# NavMergeBoard.net
KiCad netlist of a schematic drawn in Altium Designer
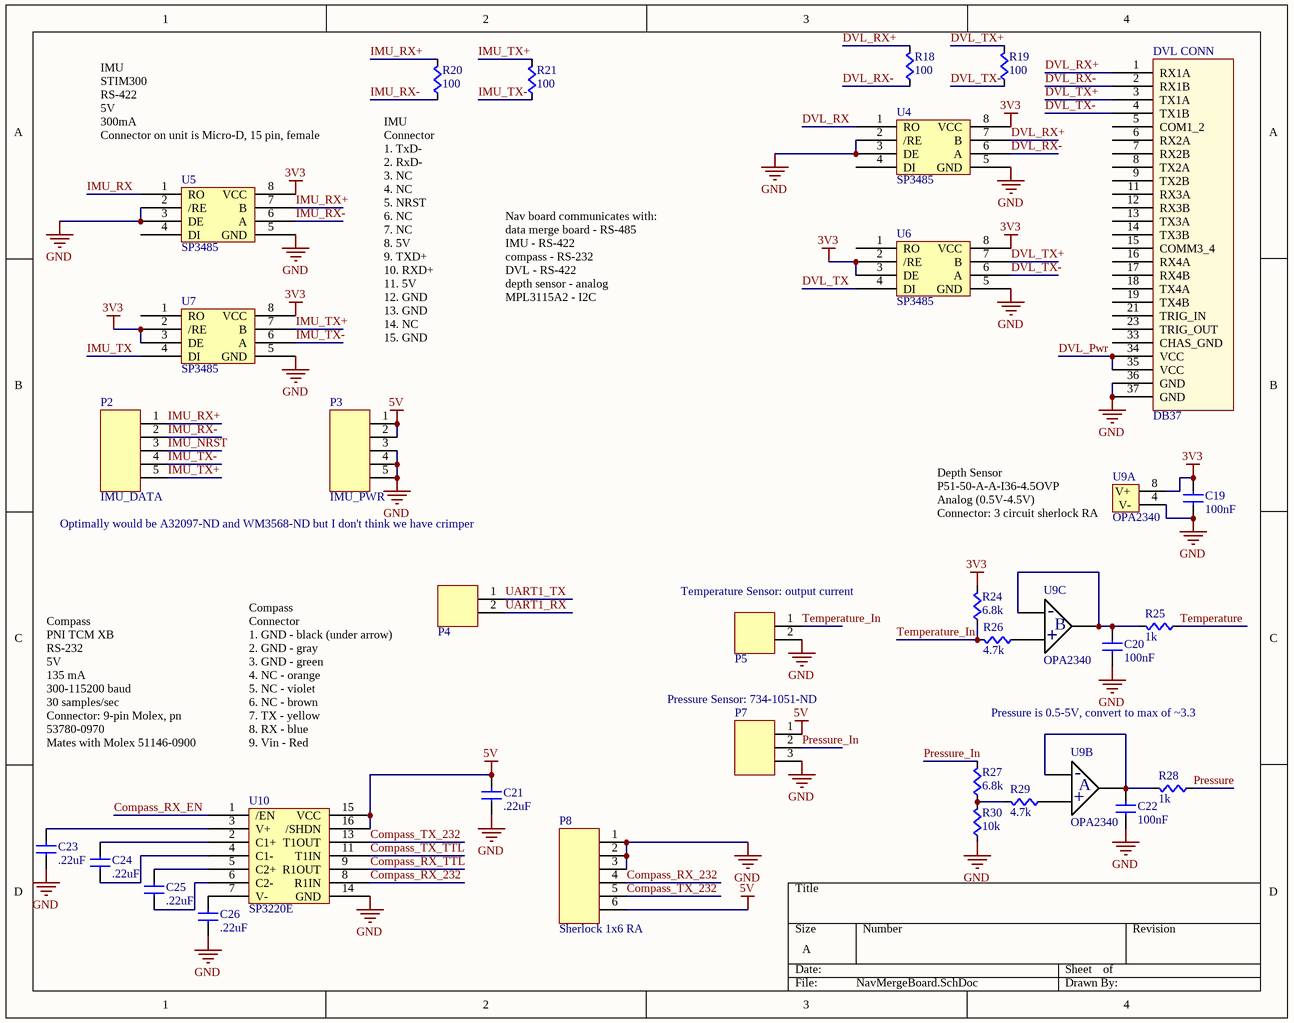
[diagram p0: NavMergeBoard.SchDoc]

(export (version "E")
  (design (tool "Eeschema 10.0.6"))
  (components
    (comp (ref "C19")
      (value "100nF")
      (footprint "CAPC0603")
      (fields (field (name "Comment") "Cap"))
      (libsource (lib "SubjuGator8") (part "Cap"))
    )
    (comp (ref "C20")
      (value "100nF")
      (footprint "CAPC0603")
      (fields (field (name "Comment") "Cap"))
      (libsource (lib "SubjuGator8") (part "Cap"))
    )
    (comp (ref "C21")
      (value ".22uF")
      (footprint "CAPC0603")
      (fields (field (name "Comment") "Cap"))
      (libsource (lib "SubjuGator8") (part "Cap"))
    )
    (comp (ref "C22")
      (value "100nF")
      (footprint "CAPC0603")
      (fields (field (name "Comment") "Cap"))
      (libsource (lib "SubjuGator8") (part "Cap"))
    )
    (comp (ref "C23")
      (value ".22uF")
      (footprint "CAPC0603")
      (fields (field (name "Comment") "Cap"))
      (libsource (lib "SubjuGator8") (part "Cap"))
    )
    (comp (ref "C24")
      (value ".22uF")
      (footprint "CAPC0603")
      (fields (field (name "Comment") "Cap"))
      (libsource (lib "SubjuGator8") (part "Cap"))
    )
    (comp (ref "C25")
      (value ".22uF")
      (footprint "CAPC0603")
      (fields (field (name "Comment") "Cap"))
      (libsource (lib "SubjuGator8") (part "Cap"))
    )
    (comp (ref "C26")
      (value ".22uF")
      (footprint "CAPC0603")
      (fields (field (name "Comment") "Cap"))
      (libsource (lib "SubjuGator8") (part "Cap"))
    )
    (comp (ref "DVL CONN")
      (value "DB37")
      (footprint "DSUB37_ FEMALE")
      (description "DVL Connector using DSUB37")
      (fields
        (field (name "MANUFACTURER") "FCI")
        (field (name "MANUFACTURER PART NUMBER") "10090098-S374VLF")
      )
      (libsource (lib "SubjuGator8") (part "DVLCONN"))
    )
    (comp (ref "P2")
      (value "MOLEX-HDR-1x5-SHERLOCK_RA")
      (footprint "MOLEX-HDR-1X5-SHERLOCK- RA")
      (fields (field (name "MANUFACTURER PART NUMBER") "0353630560") (field (name "MANUFACTURER") "Molex"))
      (libsource (lib "SubjuGator8") (part "MOLEX-HDR-1x5-SHERLOCK_RA"))
    )
    (comp (ref "P3")
      (value "MOLEX-HDR-1x5-SHERLOCK_RA")
      (footprint "MOLEX-HDR-1X5-SHERLOCK- RA")
      (fields (field (name "MANUFACTURER PART NUMBER") "0353630560") (field (name "MANUFACTURER") "Molex"))
      (libsource (lib "SubjuGator8") (part "MOLEX-HDR-1x5-SHERLOCK_RA"))
    )
    (comp (ref "P4")
      (value "2-pin Horz Sherlock")
      (footprint "MOLEX-HDR-1X2-SHERLOCK-HORZ")
      (fields
        (field (name "MANUFACTURER PART NUMBER") "0353630260")
        (field (name "MANUFACTURER") "Molex Inc")
      )
      (libsource (lib "SubjuGator8") (part "MOLEX-HDR-1x2-SHERLOCK_RA"))
    )
    (comp (ref "P5")
      (value "2-pin Horz Sherlock")
      (footprint "MOLEX-HDR-1X2-SHERLOCK-HORZ")
      (fields
        (field (name "MANUFACTURER PART NUMBER") "0353630260")
        (field (name "MANUFACTURER") "Molex Inc")
      )
      (libsource (lib "SubjuGator8") (part "MOLEX-HDR-1x2-SHERLOCK_RA"))
    )
    (comp (ref "P7")
      (value "3pos RA sherlock connector")
      (footprint "MOLEX-HDR-1X3-SHERLOCK-RA")
      (description "Header, Molex, 2mm Pitch Sherlock Header, Single Row, Right Angle 3 Circuits, Length 3.3mm")
      (fields
        (field (name "MANUFACTURER PART NUMBER") "35363-0360")
        (field (name "MANUFACTURER") "Molex Connector Corporation")
      )
      (libsource (lib "SubjuGator8") (part "MOLEX-HDR-1x3-SHERLOCK_RA"))
    )
    (comp (ref "P8")
      (value "Sherlock 1x6 RA")
      (footprint "MOLEX-HDR-1X6-SHERLOCK- RA")
      (description "CONN HEADER 6POS 2MM R/A TIN")
      (libsource (lib "SubjuGator8") (part "MOLEX-HDR-1x6-SHERLOCK_RA"))
    )
    (comp (ref "R18")
      (value "100")
      (footprint "RES0603")
      (fields (field (name "Comment") "Res"))
      (libsource (lib "SubjuGator8") (part "Res"))
    )
    (comp (ref "R19")
      (value "100")
      (footprint "RES0603")
      (fields (field (name "Comment") "Res"))
      (libsource (lib "SubjuGator8") (part "Res"))
    )
    (comp (ref "R20")
      (value "100")
      (footprint "RES0603")
      (fields (field (name "Comment") "Res"))
      (libsource (lib "SubjuGator8") (part "Res"))
    )
    (comp (ref "R21")
      (value "100")
      (footprint "RES0603")
      (fields (field (name "Comment") "Res"))
      (libsource (lib "SubjuGator8") (part "Res"))
    )
    (comp (ref "R24")
      (value "6.8k")
      (footprint "RES0603")
      (fields (field (name "Comment") "Res"))
      (libsource (lib "SubjuGator8") (part "Res"))
    )
    (comp (ref "R25")
      (value "1k")
      (footprint "RES0603")
      (fields (field (name "Comment") "Res"))
      (libsource (lib "SubjuGator8") (part "Res"))
    )
    (comp (ref "R26")
      (value "4.7k")
      (footprint "RES0603")
      (fields (field (name "Comment") "Res"))
      (libsource (lib "SubjuGator8") (part "Res"))
    )
    (comp (ref "R27")
      (value "6.8k")
      (footprint "RES0603")
      (fields (field (name "Comment") "Res"))
      (libsource (lib "SubjuGator8") (part "Res"))
    )
    (comp (ref "R28")
      (value "1k")
      (footprint "RES0603")
      (fields (field (name "Comment") "Res"))
      (libsource (lib "SubjuGator8") (part "Res"))
    )
    (comp (ref "R29")
      (value "4.7k")
      (footprint "RES0603")
      (fields (field (name "Comment") "Res"))
      (libsource (lib "SubjuGator8") (part "Res"))
    )
    (comp (ref "R30")
      (value "10k")
      (footprint "RES0603")
      (fields (field (name "Comment") "Res"))
      (libsource (lib "SubjuGator8") (part "Res"))
    )
    (comp (ref "U4")
      (value "SP3485")
      (footprint "SP3485")
      (description "IC TXRX RS485 HALF DUPLEX 8NSOIC")
      (libsource (lib "SubjuGator8") (part "SP3485"))
    )
    (comp (ref "U5")
      (value "SP3485")
      (footprint "SP3485")
      (description "IC TXRX RS485 HALF DUPLEX 8NSOIC")
      (libsource (lib "SubjuGator8") (part "SP3485"))
    )
    (comp (ref "U6")
      (value "SP3485")
      (footprint "SP3485")
      (description "IC TXRX RS485 HALF DUPLEX 8NSOIC")
      (libsource (lib "SubjuGator8") (part "SP3485"))
    )
    (comp (ref "U7")
      (value "SP3485")
      (footprint "SP3485")
      (description "IC TXRX RS485 HALF DUPLEX 8NSOIC")
      (libsource (lib "SubjuGator8") (part "SP3485"))
    )
    (comp (ref "U9")
      (value "OPA2340")
      (footprint "OPA2340")
      (description "IC OPAMP GP 5.5MHZ RRO 8SOIC")
      (libsource (lib "SubjuGator8") (part "OPA2340"))
    )
    (comp (ref "U10")
      (value "SP3220E")
      (footprint "SP3220ECY-L/TR")
      (description "IC DVR/RCVR RS232 ESD 16TSSOP")
      (libsource (lib "ICs") (part "SP3220E"))
    )
  )
  (nets
    (net (code "1") (name "/Compass_RX_232") (class "Default")
      (node (ref "P8") (pin "4") (pinfunction "4_4") (pintype "passive"))
      (node (ref "U10") (pin "8") (pinfunction "R1IN_8") (pintype "passive"))
    )
    (net (code "2") (name "/Compass_RX_EN") (class "Default")
      (node (ref "U10") (pin "1") (pinfunction "/EN_1") (pintype "passive"))
    )
    (net (code "3") (name "/Compass_RX_TTL") (class "Default")
      (node (ref "U10") (pin "9") (pinfunction "R1OUT_9") (pintype "passive"))
    )
    (net (code "4") (name "/Compass_TX_232") (class "Default")
      (node (ref "P8") (pin "5") (pinfunction "5_5") (pintype "passive"))
      (node (ref "U10") (pin "13") (pinfunction "T1OUT_13") (pintype "passive"))
    )
    (net (code "5") (name "/Compass_TX_TTL") (class "Default")
      (node (ref "U10") (pin "11") (pinfunction "T1IN_11") (pintype "passive"))
    )
    (net (code "6") (name "/DVL_Pwr") (class "Default")
      (node (ref "DVL CONN") (pin "34") (pinfunction "VCC_34") (pintype "passive"))
      (node (ref "DVL CONN") (pin "35") (pinfunction "VCC_35") (pintype "passive"))
    )
    (net (code "7") (name "/DVL_RX") (class "Default")
      (node (ref "U4") (pin "1") (pinfunction "RO_1") (pintype "passive"))
    )
    (net (code "8") (name "/DVL_RX+") (class "Default")
      (node (ref "DVL CONN") (pin "1") (pinfunction "RX1A_1") (pintype "passive"))
      (node (ref "R18") (pin "1") (pinfunction "A_1") (pintype "passive"))
      (node (ref "U4") (pin "7") (pinfunction "B_7") (pintype "passive"))
    )
    (net (code "9") (name "/DVL_RX-") (class "Default")
      (node (ref "DVL CONN") (pin "2") (pinfunction "RX1B_2") (pintype "passive"))
      (node (ref "R18") (pin "2") (pinfunction "B_2") (pintype "passive"))
      (node (ref "U4") (pin "6") (pinfunction "A_6") (pintype "passive"))
    )
    (net (code "10") (name "/DVL_TX") (class "Default")
      (node (ref "U6") (pin "4") (pinfunction "DI_4") (pintype "passive"))
    )
    (net (code "11") (name "/DVL_TX+") (class "Default")
      (node (ref "DVL CONN") (pin "3") (pinfunction "TX1A_3") (pintype "passive"))
      (node (ref "R19") (pin "1") (pinfunction "A_1") (pintype "passive"))
      (node (ref "U6") (pin "7") (pinfunction "B_7") (pintype "passive"))
    )
    (net (code "12") (name "/DVL_TX-") (class "Default")
      (node (ref "DVL CONN") (pin "4") (pinfunction "TX1B_4") (pintype "passive"))
      (node (ref "R19") (pin "2") (pinfunction "B_2") (pintype "passive"))
      (node (ref "U6") (pin "6") (pinfunction "A_6") (pintype "passive"))
    )
    (net (code "13") (name "/IMU_NRST") (class "Default")
      (node (ref "P2") (pin "3") (pinfunction "3_3") (pintype "passive"))
    )
    (net (code "14") (name "/IMU_RX") (class "Default")
      (node (ref "U5") (pin "1") (pinfunction "RO_1") (pintype "passive"))
    )
    (net (code "15") (name "/IMU_RX+") (class "Default")
      (node (ref "P2") (pin "1") (pinfunction "1_1") (pintype "passive"))
      (node (ref "R20") (pin "1") (pinfunction "A_1") (pintype "passive"))
      (node (ref "U5") (pin "7") (pinfunction "B_7") (pintype "passive"))
    )
    (net (code "16") (name "/IMU_RX-") (class "Default")
      (node (ref "P2") (pin "2") (pinfunction "2_2") (pintype "passive"))
      (node (ref "R20") (pin "2") (pinfunction "B_2") (pintype "passive"))
      (node (ref "U5") (pin "6") (pinfunction "A_6") (pintype "passive"))
    )
    (net (code "17") (name "/IMU_TX") (class "Default")
      (node (ref "U7") (pin "4") (pinfunction "DI_4") (pintype "passive"))
    )
    (net (code "18") (name "/IMU_TX+") (class "Default")
      (node (ref "P2") (pin "5") (pinfunction "5_5") (pintype "passive"))
      (node (ref "R21") (pin "1") (pinfunction "A_1") (pintype "passive"))
      (node (ref "U7") (pin "7") (pinfunction "B_7") (pintype "passive"))
    )
    (net (code "19") (name "/IMU_TX-") (class "Default")
      (node (ref "P2") (pin "4") (pinfunction "4_4") (pintype "passive"))
      (node (ref "R21") (pin "2") (pinfunction "B_2") (pintype "passive"))
      (node (ref "U7") (pin "6") (pinfunction "A_6") (pintype "passive"))
    )
    (net (code "20") (name "/Pressure") (class "Default")
      (node (ref "R28") (pin "2") (pinfunction "B_2") (pintype "passive"))
    )
    (net (code "21") (name "/Pressure_In") (class "Default")
      (node (ref "P7") (pin "2") (pinfunction "2_2") (pintype "passive"))
      (node (ref "R27") (pin "1") (pinfunction "A_1") (pintype "passive"))
    )
    (net (code "22") (name "/Temperature") (class "Default")
      (node (ref "R25") (pin "2") (pinfunction "B_2") (pintype "passive"))
    )
    (net (code "23") (name "/Temperature_In") (class "Default")
      (node (ref "P5") (pin "1") (pinfunction "1_1") (pintype "passive"))
      (node (ref "R24") (pin "2") (pinfunction "B_2") (pintype "passive"))
      (node (ref "R26") (pin "1") (pinfunction "A_1") (pintype "passive"))
    )
    (net (code "24") (name "/UART1_RX") (class "Default")
      (node (ref "P4") (pin "2") (pinfunction "2_2") (pintype "passive"))
    )
    (net (code "25") (name "/UART1_TX") (class "Default")
      (node (ref "P4") (pin "1") (pinfunction "1_1") (pintype "passive"))
    )
    (net (code "26") (name "3V3") (class "Default")
      (node (ref "C19") (pin "1") (pinfunction "A_1") (pintype "passive"))
      (node (ref "R24") (pin "1") (pinfunction "A_1") (pintype "passive"))
      (node (ref "U4") (pin "8") (pinfunction "VCC_8") (pintype "passive"))
      (node (ref "U5") (pin "8") (pinfunction "VCC_8") (pintype "passive"))
      (node (ref "U6") (pin "2") (pinfunction "/RE_2") (pintype "passive"))
      (node (ref "U6") (pin "3") (pinfunction "DE_3") (pintype "passive"))
      (node (ref "U6") (pin "8") (pinfunction "VCC_8") (pintype "passive"))
      (node (ref "U7") (pin "2") (pinfunction "/RE_2") (pintype "passive"))
      (node (ref "U7") (pin "3") (pinfunction "DE_3") (pintype "passive"))
      (node (ref "U7") (pin "8") (pinfunction "VCC_8") (pintype "passive"))
      (node (ref "U9") (pin "8") (pinfunction "V+_8") (pintype "passive"))
    )
    (net (code "27") (name "5V") (class "Default")
      (node (ref "C21") (pin "1") (pinfunction "A_1") (pintype "passive"))
      (node (ref "P3") (pin "1") (pinfunction "1_1") (pintype "passive"))
      (node (ref "P3") (pin "2") (pinfunction "2_2") (pintype "passive"))
      (node (ref "P7") (pin "1") (pinfunction "1_1") (pintype "passive"))
      (node (ref "P8") (pin "6") (pinfunction "6_6") (pintype "passive"))
      (node (ref "U10") (pin "15") (pinfunction "VCC_15") (pintype "passive"))
      (node (ref "U10") (pin "16") (pinfunction "/SHDN_16") (pintype "passive"))
    )
    (net (code "28") (name "GND") (class "Default")
      (node (ref "C19") (pin "2") (pinfunction "B_2") (pintype "passive"))
      (node (ref "C20") (pin "2") (pinfunction "B_2") (pintype "passive"))
      (node (ref "C21") (pin "2") (pinfunction "B_2") (pintype "passive"))
      (node (ref "C22") (pin "2") (pinfunction "B_2") (pintype "passive"))
      (node (ref "C23") (pin "2") (pinfunction "B_2") (pintype "passive"))
      (node (ref "C26") (pin "2") (pinfunction "B_2") (pintype "passive"))
      (node (ref "DVL CONN") (pin "36") (pinfunction "GND_36") (pintype "passive"))
      (node (ref "DVL CONN") (pin "37") (pinfunction "GND_37") (pintype "passive"))
      (node (ref "P3") (pin "3") (pinfunction "3_3") (pintype "passive"))
      (node (ref "P3") (pin "4") (pinfunction "4_4") (pintype "passive"))
      (node (ref "P3") (pin "5") (pinfunction "5_5") (pintype "passive"))
      (node (ref "P5") (pin "2") (pinfunction "2_2") (pintype "passive"))
      (node (ref "P7") (pin "3") (pinfunction "3_3") (pintype "passive"))
      (node (ref "P8") (pin "1") (pinfunction "1_1") (pintype "passive"))
      (node (ref "P8") (pin "2") (pinfunction "2_2") (pintype "passive"))
      (node (ref "P8") (pin "3") (pinfunction "3_3") (pintype "passive"))
      (node (ref "R30") (pin "2") (pinfunction "B_2") (pintype "passive"))
      (node (ref "U10") (pin "14") (pinfunction "GND_14") (pintype "passive"))
      (node (ref "U4") (pin "2") (pinfunction "/RE_2") (pintype "passive"))
      (node (ref "U4") (pin "3") (pinfunction "DE_3") (pintype "passive"))
      (node (ref "U4") (pin "5") (pinfunction "GND_5") (pintype "passive"))
      (node (ref "U5") (pin "2") (pinfunction "/RE_2") (pintype "passive"))
      (node (ref "U5") (pin "3") (pinfunction "DE_3") (pintype "passive"))
      (node (ref "U5") (pin "5") (pinfunction "GND_5") (pintype "passive"))
      (node (ref "U6") (pin "5") (pinfunction "GND_5") (pintype "passive"))
      (node (ref "U7") (pin "5") (pinfunction "GND_5") (pintype "passive"))
      (node (ref "U9") (pin "4") (pinfunction "V-_4") (pintype "passive"))
    )
    (net (code "29") (name "Net-(C20-A)") (class "Default")
      (node (ref "C20") (pin "1") (pinfunction "A_1") (pintype "passive"))
      (node (ref "R25") (pin "1") (pinfunction "A_1") (pintype "passive"))
      (node (ref "U9") (pin "6") (pinfunction "BIn-_6") (pintype "passive"))
      (node (ref "U9") (pin "7") (pinfunction "BOut_7") (pintype "passive"))
    )
    (net (code "30") (name "Net-(C22-A)") (class "Default")
      (node (ref "C22") (pin "1") (pinfunction "A_1") (pintype "passive"))
      (node (ref "R28") (pin "1") (pinfunction "A_1") (pintype "passive"))
      (node (ref "U9") (pin "1") (pinfunction "AOut_1") (pintype "passive"))
      (node (ref "U9") (pin "2") (pinfunction "AIn-_2") (pintype "passive"))
    )
    (net (code "31") (name "Net-(C23-A)") (class "Default")
      (node (ref "C23") (pin "1") (pinfunction "A_1") (pintype "passive"))
      (node (ref "U10") (pin "3") (pinfunction "V+_3") (pintype "passive"))
    )
    (net (code "32") (name "Net-(C24-A)") (class "Default")
      (node (ref "C24") (pin "1") (pinfunction "A_1") (pintype "passive"))
      (node (ref "U10") (pin "2") (pinfunction "C1+_2") (pintype "passive"))
    )
    (net (code "33") (name "Net-(C24-B)") (class "Default")
      (node (ref "C24") (pin "2") (pinfunction "B_2") (pintype "passive"))
      (node (ref "U10") (pin "4") (pinfunction "C1-_4") (pintype "passive"))
    )
    (net (code "34") (name "Net-(C25-A)") (class "Default")
      (node (ref "C25") (pin "1") (pinfunction "A_1") (pintype "passive"))
      (node (ref "U10") (pin "5") (pinfunction "C2+_5") (pintype "passive"))
    )
    (net (code "35") (name "Net-(C25-B)") (class "Default")
      (node (ref "C25") (pin "2") (pinfunction "B_2") (pintype "passive"))
      (node (ref "U10") (pin "6") (pinfunction "C2-_6") (pintype "passive"))
    )
    (net (code "36") (name "Net-(C26-A)") (class "Default")
      (node (ref "C26") (pin "1") (pinfunction "A_1") (pintype "passive"))
      (node (ref "U10") (pin "7") (pinfunction "V-_7") (pintype "passive"))
    )
    (net (code "37") (name "Net-(R26-B)") (class "Default")
      (node (ref "R26") (pin "2") (pinfunction "B_2") (pintype "passive"))
      (node (ref "U9") (pin "5") (pinfunction "BIn+_5") (pintype "passive"))
    )
    (net (code "38") (name "Net-(R27-B)") (class "Default")
      (node (ref "R27") (pin "2") (pinfunction "B_2") (pintype "passive"))
      (node (ref "R29") (pin "1") (pinfunction "A_1") (pintype "passive"))
      (node (ref "R30") (pin "1") (pinfunction "A_1") (pintype "passive"))
    )
    (net (code "39") (name "Net-(R29-B)") (class "Default")
      (node (ref "R29") (pin "2") (pinfunction "B_2") (pintype "passive"))
      (node (ref "U9") (pin "3") (pinfunction "AIn+_3") (pintype "passive"))
    )
    (net (code "40") (name "unconnected-(DVL CONN-CHAS_GND-Pad33)") (class "Default")
      (node (ref "DVL CONN") (pin "33") (pinfunction "CHAS_GND_33") (pintype "passive"))
    )
    (net (code "41") (name "unconnected-(DVL CONN-COM1_2-Pad5)") (class "Default")
      (node (ref "DVL CONN") (pin "5") (pinfunction "COM1_2_5") (pintype "passive"))
    )
    (net (code "42") (name "unconnected-(DVL CONN-COMM3_4-Pad15)") (class "Default")
      (node (ref "DVL CONN") (pin "15") (pinfunction "COMM3_4_15") (pintype "passive"))
    )
    (net (code "43") (name "unconnected-(DVL CONN-RX2A-Pad6)") (class "Default")
      (node (ref "DVL CONN") (pin "6") (pinfunction "RX2A_6") (pintype "passive"))
    )
    (net (code "44") (name "unconnected-(DVL CONN-RX2B-Pad7)") (class "Default")
      (node (ref "DVL CONN") (pin "7") (pinfunction "RX2B_7") (pintype "passive"))
    )
    (net (code "45") (name "unconnected-(DVL CONN-RX3A-Pad11)") (class "Default")
      (node (ref "DVL CONN") (pin "11") (pinfunction "RX3A_11") (pintype "passive"))
    )
    (net (code "46") (name "unconnected-(DVL CONN-RX3B-Pad12)") (class "Default")
      (node (ref "DVL CONN") (pin "12") (pinfunction "RX3B_12") (pintype "passive"))
    )
    (net (code "47") (name "unconnected-(DVL CONN-RX4A-Pad16)") (class "Default")
      (node (ref "DVL CONN") (pin "16") (pinfunction "RX4A_16") (pintype "passive"))
    )
    (net (code "48") (name "unconnected-(DVL CONN-RX4B-Pad17)") (class "Default")
      (node (ref "DVL CONN") (pin "17") (pinfunction "RX4B_17") (pintype "passive"))
    )
    (net (code "49") (name "unconnected-(DVL CONN-TRIG_IN-Pad21)") (class "Default")
      (node (ref "DVL CONN") (pin "21") (pinfunction "TRIG_IN_21") (pintype "passive"))
    )
    (net (code "50") (name "unconnected-(DVL CONN-TRIG_OUT-Pad23)") (class "Default")
      (node (ref "DVL CONN") (pin "23") (pinfunction "TRIG_OUT_23") (pintype "passive"))
    )
    (net (code "51") (name "unconnected-(DVL CONN-TX2A-Pad8)") (class "Default")
      (node (ref "DVL CONN") (pin "8") (pinfunction "TX2A_8") (pintype "passive"))
    )
    (net (code "52") (name "unconnected-(DVL CONN-TX2B-Pad9)") (class "Default")
      (node (ref "DVL CONN") (pin "9") (pinfunction "TX2B_9") (pintype "passive"))
    )
    (net (code "53") (name "unconnected-(DVL CONN-TX3A-Pad13)") (class "Default")
      (node (ref "DVL CONN") (pin "13") (pinfunction "TX3A_13") (pintype "passive"))
    )
    (net (code "54") (name "unconnected-(DVL CONN-TX3B-Pad14)") (class "Default")
      (node (ref "DVL CONN") (pin "14") (pinfunction "TX3B_14") (pintype "passive"))
    )
    (net (code "55") (name "unconnected-(DVL CONN-TX4A-Pad18)") (class "Default")
      (node (ref "DVL CONN") (pin "18") (pinfunction "TX4A_18") (pintype "passive"))
    )
    (net (code "56") (name "unconnected-(DVL CONN-TX4B-Pad19)") (class "Default")
      (node (ref "DVL CONN") (pin "19") (pinfunction "TX4B_19") (pintype "passive"))
    )
    (net (code "57") (name "unconnected-(U4-DI-Pad4)") (class "Default")
      (node (ref "U4") (pin "4") (pinfunction "DI_4") (pintype "passive"))
    )
    (net (code "58") (name "unconnected-(U5-DI-Pad4)") (class "Default")
      (node (ref "U5") (pin "4") (pinfunction "DI_4") (pintype "passive"))
    )
    (net (code "59") (name "unconnected-(U6-RO-Pad1)") (class "Default")
      (node (ref "U6") (pin "1") (pinfunction "RO_1") (pintype "passive"))
    )
    (net (code "60") (name "unconnected-(U7-RO-Pad1)") (class "Default")
      (node (ref "U7") (pin "1") (pinfunction "RO_1") (pintype "passive"))
    )
  )
)
